# battery_charger_ni_mh.net
KiCad netlist of a schematic drawn in Altium Designer
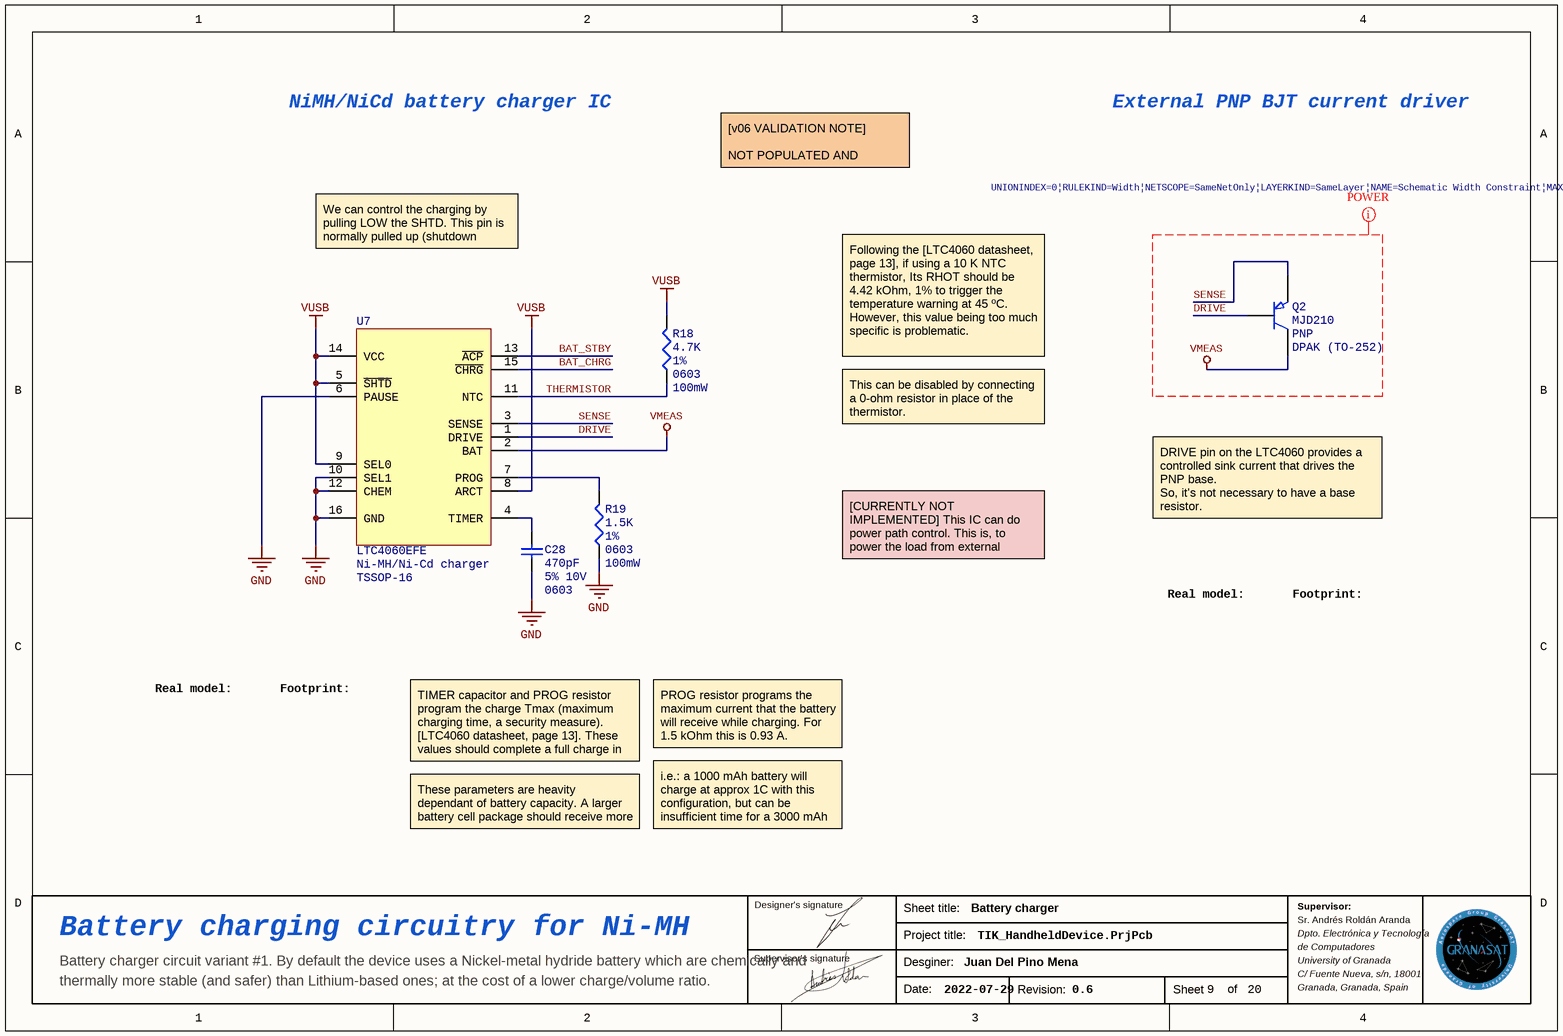
[diagram p0: battery_charger_ni_mh.SchDoc]

(export (version "E")
  (design (tool "Eeschema 10.0.6"))
  (components
    (comp (ref "C28")
      (value "470pF")
      (footprint "CAP 0603_1608")
      (description "Ceramic cap size 0805")
      (fields
        (field (name "TOLERANCE") "5% 10V")
        (field (name "PACKAGEDESCRIPTION") "0603")
        (field (name "Comment") "Cap_cer_0603_470pF_5%")
      )
      (libsource (lib "tik_handheld_schlib") (part "Cap_cer_0603_470pF_5%"))
    )
    (comp (ref "Q2")
      (value "PNP BJT MJD210 transistor")
      (footprint "DPAK TO-252 MJD210")
      (description "MJD210 PNP BJT transistor DPAK (decawatt) 5A dc")
      (fields
        (field (name "PART") "MJD210")
        (field (name "TYPE") "PNP")
        (field (name "PACKAGEDESCRIPTION") "DPAK (TO-252)")
      )
      (libsource (lib "tik_handheld_schlib") (part "PNP BJT MJD210 transistor"))
    )
    (comp (ref "R18")
      (value "4.7K")
      (footprint "RES 0603_1608")
      (description "Res size 0603 SMD mounting, low power")
      (fields
        (field (name "TOLERANCE") "1%")
        (field (name "PACKAGEDESCRIPTION") "0603")
        (field (name "POWERDISIPATED") "100mW")
        (field (name "Comment") "Res_0603_4.7K_1%_100mW")
      )
      (libsource (lib "tik_handheld_schlib") (part "Res_0603_4.7K_1%_100mW"))
    )
    (comp (ref "R19")
      (value "1.5K")
      (footprint "RES 0603_1608")
      (description "Res size 0603 SMD mounting, low power")
      (fields
        (field (name "TOLERANCE") "1%")
        (field (name "PACKAGEDESCRIPTION") "0603")
        (field (name "POWERDISIPATED") "100mW")
        (field (name "Comment") "Res_0603_1.5K_1%_100mW")
      )
      (libsource (lib "tik_handheld_schlib") (part "Res_0603_1.5K_1%_100mW"))
    )
    (comp (ref "U7")
      (value "IC LTC4060EFE Bat NiMH charger")
      (footprint "TSSOP-16 LTC4060EFE")
      (description "LTC4060EFE")
      (fields
        (field (name "PART") "LTC4060EFE")
        (field (name "PACKAGEDESCRIPTION") "TSSOP-16")
        (field (name "DESC") "Ni-MH/Ni-Cd charger")
      )
      (libsource (lib "tik_handheld_schlib") (part "IC LTC4060EFE Bat NiMH charger"))
    )
  )
  (nets
    (net (code "1") (name "/BAT_CHRG") (class "Default")
      (node (ref "U7") (pin "15") (pinfunction "~{CHRG}_15") (pintype "passive"))
    )
    (net (code "2") (name "/BAT_STBY") (class "Default")
      (node (ref "U7") (pin "13") (pinfunction "~{ACP}_13") (pintype "passive"))
    )
    (net (code "3") (name "/DRIVE") (class "Default")
      (node (ref "Q2") (pin "1") (pinfunction "B_1") (pintype "passive"))
      (node (ref "U7") (pin "1") (pinfunction "DRIVE_1") (pintype "passive"))
    )
    (net (code "4") (name "/SENSE") (class "Default")
      (node (ref "Q2") (pin "3") (pinfunction "E_3") (pintype "passive"))
      (node (ref "U7") (pin "3") (pinfunction "SENSE_3") (pintype "passive"))
    )
    (net (code "5") (name "/THERMISTOR") (class "Default")
      (node (ref "R18") (pin "1") (pinfunction "1_1") (pintype "passive"))
      (node (ref "U7") (pin "11") (pinfunction "NTC_11") (pintype "passive"))
    )
    (net (code "6") (name "GND") (class "Default")
      (node (ref "C28") (pin "1") (pinfunction "1_1") (pintype "passive"))
      (node (ref "R19") (pin "1") (pinfunction "1_1") (pintype "passive"))
      (node (ref "U7") (pin "10") (pinfunction "SEL1_10") (pintype "passive"))
      (node (ref "U7") (pin "12") (pinfunction "CHEM_12") (pintype "passive"))
      (node (ref "U7") (pin "16") (pinfunction "GND_16") (pintype "passive"))
      (node (ref "U7") (pin "6") (pinfunction "PAUSE_6") (pintype "passive"))
    )
    (net (code "7") (name "Net-(U7-PROG)") (class "Default")
      (node (ref "R19") (pin "2") (pinfunction "2_2") (pintype "passive"))
      (node (ref "U7") (pin "7") (pinfunction "PROG_7") (pintype "passive"))
    )
    (net (code "8") (name "Net-(U7-TIMER)") (class "Default")
      (node (ref "C28") (pin "2") (pinfunction "2_2") (pintype "passive"))
      (node (ref "U7") (pin "4") (pinfunction "TIMER_4") (pintype "passive"))
    )
    (net (code "9") (name "VMEAS") (class "Default")
      (node (ref "Q2") (pin "4") (pinfunction "C_4") (pintype "passive"))
      (node (ref "U7") (pin "2") (pinfunction "BAT_2") (pintype "passive"))
    )
    (net (code "10") (name "VUSB") (class "Default")
      (node (ref "R18") (pin "2") (pinfunction "2_2") (pintype "passive"))
      (node (ref "U7") (pin "14") (pinfunction "VCC_14") (pintype "passive"))
      (node (ref "U7") (pin "5") (pinfunction "~{SHTD}_5") (pintype "passive"))
      (node (ref "U7") (pin "8") (pinfunction "ARCT_8") (pintype "passive"))
      (node (ref "U7") (pin "9") (pinfunction "SEL0_9") (pintype "passive"))
    )
  )
)
